# LED_Adapter_In_Konflikt_stehende_Kopie_v.net
KiCad netlist of a schematic drawn in Altium Designer
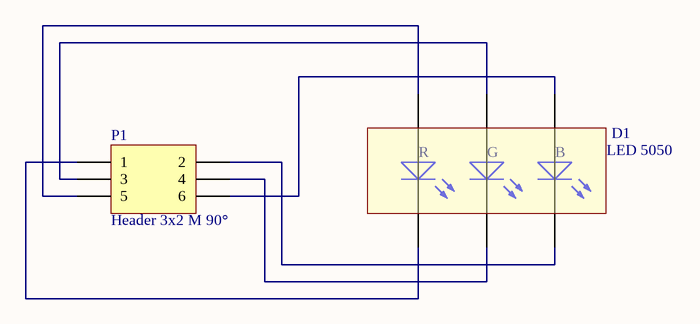
[diagram p0: LED_Adapter (In Konflikt stehende Kopie von Josua Schmid 2012-06-01).SchDoc]

(export (version "E")
  (design (tool "Eeschema 10.0.6"))
  (components
    (comp (ref "D1")
      (value "LED 5050")
      (footprint "PLCC6")
      (description "SMD PLCC-6 20mA 5050")
      (libsource (lib "HQ_Library") (part "LED RGB 5050"))
    )
    (comp (ref "P1")
      (value "Header 3x2 M 90°")
      (footprint "Pin Header 3x2 M 90°")
      (description "Header, 6-Pin, Male 90°")
      (libsource (lib "HQ_Library") (part "Header 3x2 M 90°"))
    )
  )
  (nets
    (net (code "1") (name "Net-(D1-A_B)") (class "Default")
      (node (ref "D1") (pin "6") (pinfunction "A_B_6") (pintype "passive"))
      (node (ref "P1") (pin "6") (pinfunction "6_6") (pintype "passive"))
    )
    (net (code "2") (name "Net-(D1-A_G)") (class "Default")
      (node (ref "D1") (pin "4") (pinfunction "A_G_4") (pintype "passive"))
      (node (ref "P1") (pin "3") (pinfunction "3_3") (pintype "passive"))
    )
    (net (code "3") (name "Net-(D1-A_R)") (class "Default")
      (node (ref "D1") (pin "2") (pinfunction "A_R_2") (pintype "passive"))
      (node (ref "P1") (pin "5") (pinfunction "5_5") (pintype "passive"))
    )
    (net (code "4") (name "Net-(D1-K_B)") (class "Default")
      (node (ref "D1") (pin "5") (pinfunction "K_B_5") (pintype "passive"))
      (node (ref "P1") (pin "2") (pinfunction "2_2") (pintype "passive"))
    )
    (net (code "5") (name "Net-(D1-K_G)") (class "Default")
      (node (ref "D1") (pin "3") (pinfunction "K_G_3") (pintype "passive"))
      (node (ref "P1") (pin "4") (pinfunction "4_4") (pintype "passive"))
    )
    (net (code "6") (name "Net-(D1-K_R)") (class "Default")
      (node (ref "D1") (pin "1") (pinfunction "K_R_1") (pintype "passive"))
      (node (ref "P1") (pin "1") (pinfunction "1_1") (pintype "passive"))
    )
  )
)
